# SCH_fig3_2021-11-24.net
KiCad netlist of a schematic drawn in EasyEDA
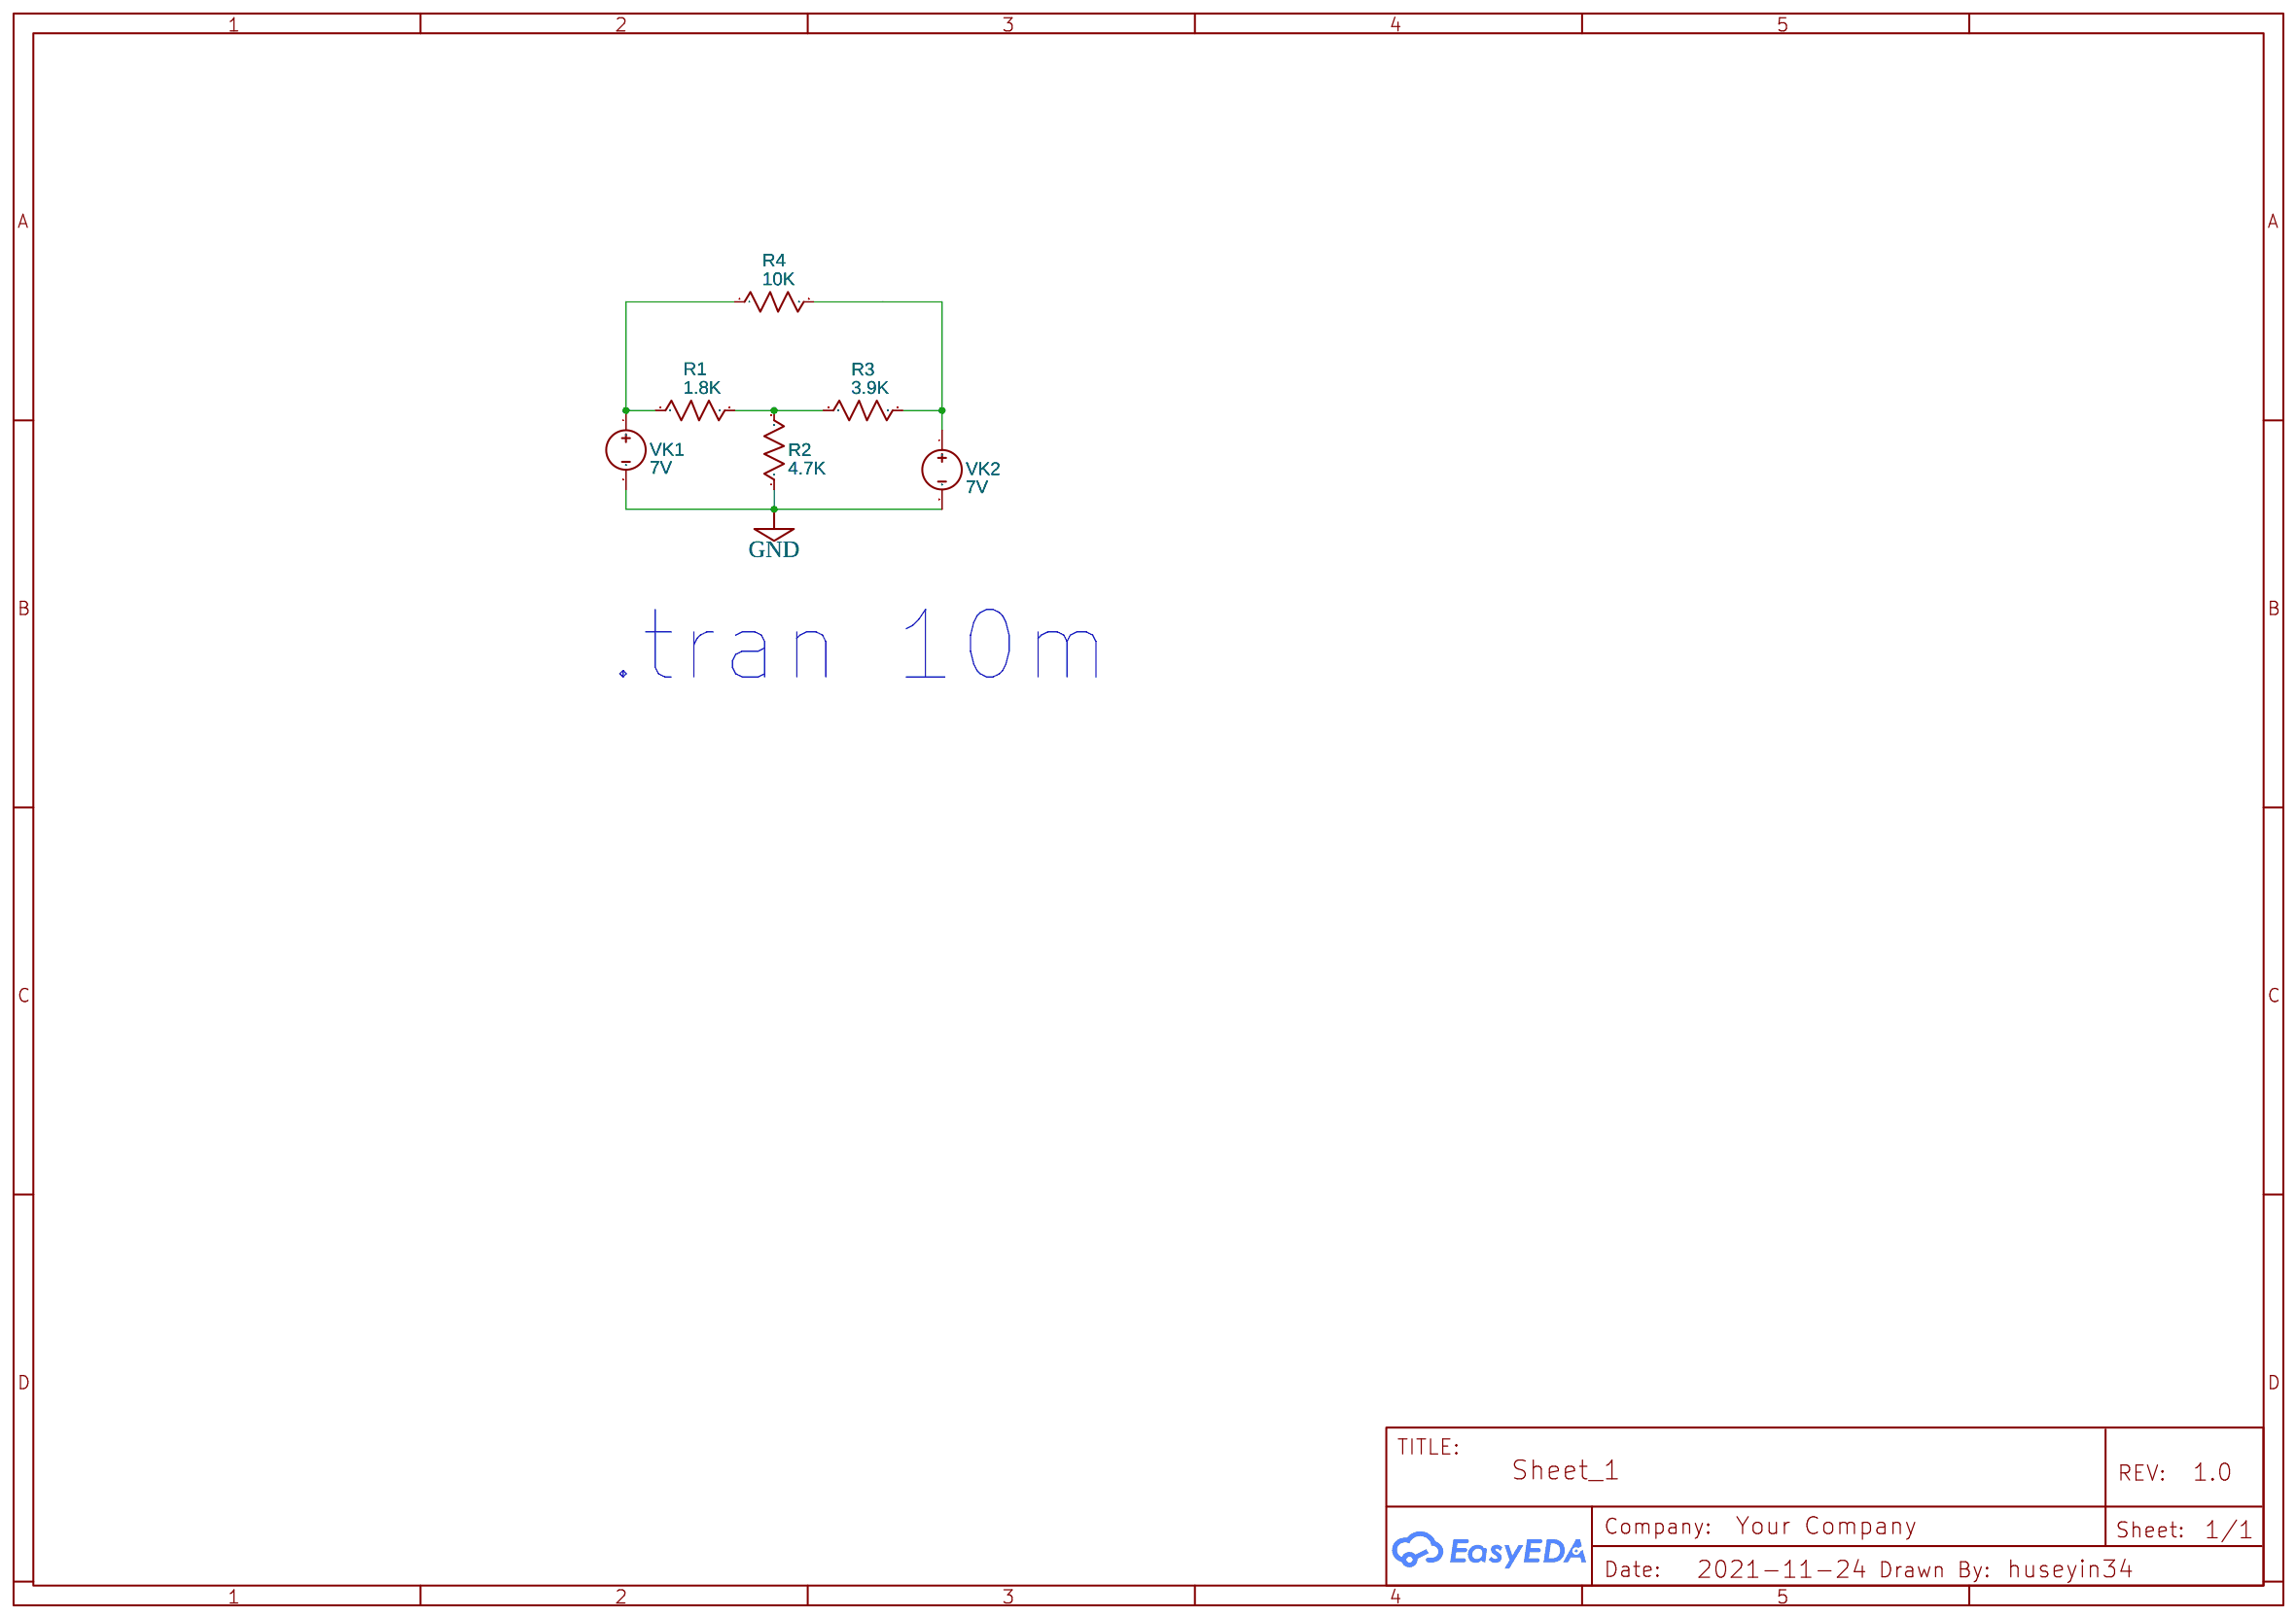
[diagram p0: schematic sheet]

(export (version "E")
  (design (tool "Eeschema 10.0.6"))
  (components
    (comp (ref "R1") (value "1.8K") (libsource (lib "") (part "Resistor_US_2")))
    (comp (ref "R2") (value "4.7K") (libsource (lib "") (part "Resistor_US")))
    (comp (ref "R3") (value "3.9K") (libsource (lib "") (part "Resistor_US_1")))
    (comp (ref "R4") (value "10K") (libsource (lib "") (part "Resistor_US_2")))
    (comp (ref "VK1") (value "7V") (libsource (lib "") (part "VDC")))
    (comp (ref "VK2") (value "7V") (libsource (lib "") (part "VDC")))
  )
  (nets
    (net (code "1") (name "GND") (class "Default")
      (node (ref "R2") (pin "1") (pinfunction "1_1") (pintype "unspecified"))
      (node (ref "VK1") (pin "2") (pinfunction "2_2") (pintype "unspecified"))
      (node (ref "VK2") (pin "2") (pinfunction "2_2") (pintype "unspecified"))
    )
    (net (code "2") (name "Net-(R1-Pad1)") (class "Default")
      (node (ref "R1") (pin "1") (pinfunction "1_1") (pintype "unspecified"))
      (node (ref "R4") (pin "1") (pinfunction "1_1") (pintype "unspecified"))
      (node (ref "VK1") (pin "1") (pinfunction "1_1") (pintype "unspecified"))
    )
    (net (code "3") (name "Net-(R1-Pad2)") (class "Default")
      (node (ref "R1") (pin "2") (pinfunction "2_2") (pintype "unspecified"))
      (node (ref "R2") (pin "2") (pinfunction "2_2") (pintype "unspecified"))
      (node (ref "R3") (pin "2") (pinfunction "2_2") (pintype "unspecified"))
    )
    (net (code "4") (name "Net-(R3-Pad1)") (class "Default")
      (node (ref "R3") (pin "1") (pinfunction "1_1") (pintype "unspecified"))
      (node (ref "R4") (pin "2") (pinfunction "2_2") (pintype "unspecified"))
      (node (ref "VK2") (pin "1") (pinfunction "1_1") (pintype "unspecified"))
    )
  )
)
